# SimpleNode32.net
KiCad netlist of a schematic drawn in Altium Designer
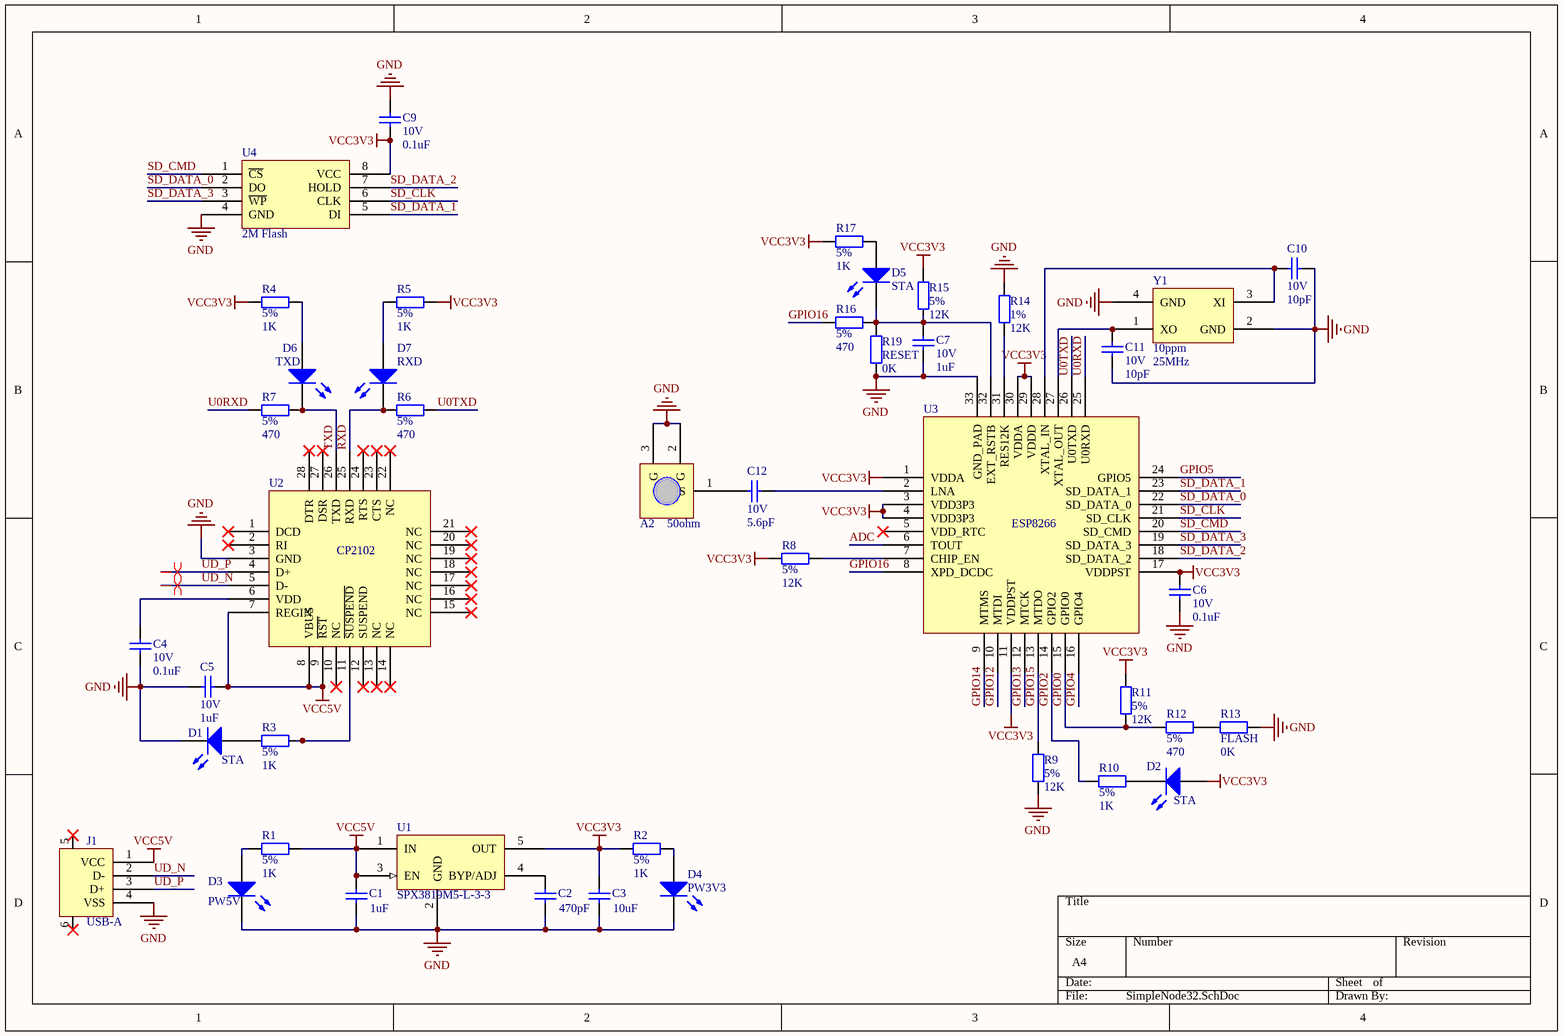
[diagram p0: SimpleNode32.SchDoc]

(export (version "E")
  (design (tool "Eeschema 10.0.6"))
  (components
    (comp (ref "A2")
      (value "50ohm")
      (footprint "IPEX-1 底座")
      (description "IPEX-1 底座")
      (libsource (lib "基础连接件") (part "IPEX-1 底座"))
    )
    (comp (ref "C1")
      (value "1uF")
      (footprint "C0402")
      (description "贴片无极性电容")
      (fields (field (name "Comment") "105"))
      (libsource (lib "基础元器件") (part "贴片无极性电容"))
    )
    (comp (ref "C2")
      (value "470pF")
      (footprint "C0402")
      (description "贴片无极性电容")
      (fields (field (name "Comment") "CAP"))
      (libsource (lib "基础元器件") (part "贴片无极性电容"))
    )
    (comp (ref "C3")
      (value "10uF")
      (footprint "C0402")
      (description "贴片无极性电容")
      (fields (field (name "Comment") "CAP"))
      (libsource (lib "基础元器件") (part "贴片无极性电容"))
    )
    (comp (ref "C4")
      (value "10V")
      (footprint "C0402")
      (description "贴片无极性电容")
      (fields (field (name "ALTIUM_VALUE") "0.1uF"))
      (libsource (lib "基础元器件") (part "贴片无极性电容"))
    )
    (comp (ref "C5")
      (value "10V")
      (footprint "C0402")
      (description "贴片无极性电容")
      (fields (field (name "ALTIUM_VALUE") "1uF"))
      (libsource (lib "基础元器件") (part "贴片无极性电容"))
    )
    (comp (ref "C6")
      (value "10V")
      (footprint "C0402")
      (description "贴片无极性电容")
      (fields (field (name "ALTIUM_VALUE") "0.1uF"))
      (libsource (lib "基础元器件") (part "贴片无极性电容"))
    )
    (comp (ref "C7")
      (value "10V")
      (footprint "C0402")
      (description "贴片无极性电容")
      (fields (field (name "ALTIUM_VALUE") "1uF"))
      (libsource (lib "基础元器件") (part "贴片无极性电容"))
    )
    (comp (ref "C9")
      (value "10V")
      (footprint "C0402")
      (description "贴片无极性电容")
      (fields (field (name "ALTIUM_VALUE") "0.1uF"))
      (libsource (lib "基础元器件") (part "贴片无极性电容"))
    )
    (comp (ref "C10")
      (value "10V")
      (footprint "C0402")
      (description "贴片无极性电容")
      (fields (field (name "ALTIUM_VALUE") "10pF"))
      (libsource (lib "基础元器件") (part "贴片无极性电容"))
    )
    (comp (ref "C11")
      (value "10V")
      (footprint "C0402")
      (description "贴片无极性电容")
      (fields (field (name "ALTIUM_VALUE") "10pF"))
      (libsource (lib "基础元器件") (part "贴片无极性电容"))
    )
    (comp (ref "C12")
      (value "10V")
      (footprint "C0402")
      (description "贴片无极性电容")
      (fields (field (name "ALTIUM_VALUE") "5.6pF"))
      (libsource (lib "基础元器件") (part "贴片无极性电容"))
    )
    (comp (ref "D1")
      (value "STA")
      (footprint "LED0402")
      (description "贴片发光二级管")
      (libsource (lib "基础元器件") (part "贴片发光二级管"))
    )
    (comp (ref "D2")
      (value "STA")
      (footprint "LED0402")
      (description "贴片发光二级管")
      (libsource (lib "基础元器件") (part "贴片发光二级管"))
    )
    (comp (ref "D3")
      (value "PW5V")
      (footprint "LED0402")
      (description "贴片发光二级管")
      (libsource (lib "基础元器件") (part "贴片发光二级管"))
    )
    (comp (ref "D4")
      (value "PW3V3")
      (footprint "LED0402")
      (description "贴片发光二级管")
      (libsource (lib "基础元器件") (part "贴片发光二级管"))
    )
    (comp (ref "D5")
      (value "STA")
      (footprint "LED0402")
      (description "贴片发光二级管")
      (libsource (lib "基础元器件") (part "贴片发光二级管"))
    )
    (comp (ref "D6")
      (value "TXD")
      (footprint "LED0402")
      (description "贴片发光二级管")
      (libsource (lib "基础元器件") (part "贴片发光二级管"))
    )
    (comp (ref "D7")
      (value "RXD")
      (footprint "LED0402")
      (description "贴片发光二级管")
      (libsource (lib "基础元器件") (part "贴片发光二级管"))
    )
    (comp (ref "J1")
      (value "USB-A")
      (footprint "USB 2.0 Type A 公头 沉板")
      (description "USB-A 公头")
      (libsource (lib "基础连接件") (part "USB-A 公头"))
    )
    (comp (ref "R1")
      (value "5%")
      (footprint "R0402")
      (description "贴片电阻")
      (fields (field (name "ALTIUM_VALUE") "1K"))
      (libsource (lib "") (part "贴片电阻_1"))
    )
    (comp (ref "R2")
      (value "5%")
      (footprint "R0402")
      (description "贴片电阻")
      (fields (field (name "ALTIUM_VALUE") "1K"))
      (libsource (lib "") (part "贴片电阻_1"))
    )
    (comp (ref "R3")
      (value "5%")
      (footprint "R0402")
      (description "贴片电阻")
      (fields (field (name "ALTIUM_VALUE") "1K"))
      (libsource (lib "") (part "贴片电阻_1"))
    )
    (comp (ref "R4")
      (value "5%")
      (footprint "R0402")
      (description "贴片电阻")
      (fields (field (name "ALTIUM_VALUE") "1K"))
      (libsource (lib "") (part "贴片电阻_1"))
    )
    (comp (ref "R5")
      (value "5%")
      (footprint "R0402")
      (description "贴片电阻")
      (fields (field (name "ALTIUM_VALUE") "1K"))
      (libsource (lib "") (part "贴片电阻_1"))
    )
    (comp (ref "R6")
      (value "5%")
      (footprint "R0402")
      (description "贴片电阻")
      (fields (field (name "ALTIUM_VALUE") "470"))
      (libsource (lib "") (part "贴片电阻_1"))
    )
    (comp (ref "R7")
      (value "5%")
      (footprint "R0402")
      (description "贴片电阻")
      (fields (field (name "ALTIUM_VALUE") "470"))
      (libsource (lib "") (part "贴片电阻_1"))
    )
    (comp (ref "R8")
      (value "5%")
      (footprint "R0402")
      (description "贴片电阻")
      (fields (field (name "ALTIUM_VALUE") "12K"))
      (libsource (lib "") (part "贴片电阻_2"))
    )
    (comp (ref "R9")
      (value "5%")
      (footprint "R0402")
      (description "贴片电阻")
      (fields (field (name "ALTIUM_VALUE") "12K"))
      (libsource (lib "基础元器件") (part "贴片电阻"))
    )
    (comp (ref "R10")
      (value "5%")
      (footprint "R0402")
      (description "贴片电阻")
      (fields (field (name "ALTIUM_VALUE") "1K"))
      (libsource (lib "") (part "贴片电阻_1"))
    )
    (comp (ref "R11")
      (value "5%")
      (footprint "R0402")
      (description "贴片电阻")
      (fields (field (name "ALTIUM_VALUE") "12K"))
      (libsource (lib "基础元器件") (part "贴片电阻"))
    )
    (comp (ref "R12")
      (value "5%")
      (footprint "R0402")
      (description "贴片电阻")
      (fields (field (name "ALTIUM_VALUE") "470"))
      (libsource (lib "") (part "贴片电阻_2"))
    )
    (comp (ref "R13")
      (value "FLASH")
      (footprint "R0402")
      (description "贴片电阻")
      (fields (field (name "ALTIUM_VALUE") "0K"))
      (libsource (lib "") (part "贴片电阻_1"))
    )
    (comp (ref "R14")
      (value "1%")
      (footprint "R0402")
      (description "贴片电阻")
      (fields (field (name "ALTIUM_VALUE") "12K"))
      (libsource (lib "基础元器件") (part "贴片电阻"))
    )
    (comp (ref "R15")
      (value "5%")
      (footprint "R0402")
      (description "贴片电阻")
      (fields (field (name "ALTIUM_VALUE") "12K"))
      (libsource (lib "基础元器件") (part "贴片电阻"))
    )
    (comp (ref "R16")
      (value "5%")
      (footprint "R0402")
      (description "贴片电阻")
      (fields (field (name "ALTIUM_VALUE") "470"))
      (libsource (lib "") (part "贴片电阻_1"))
    )
    (comp (ref "R17")
      (value "5%")
      (footprint "R0402")
      (description "贴片电阻")
      (fields (field (name "ALTIUM_VALUE") "1K"))
      (libsource (lib "") (part "贴片电阻_2"))
    )
    (comp (ref "R19")
      (value "RESET")
      (footprint "R0402")
      (description "贴片电阻")
      (fields (field (name "ALTIUM_VALUE") "0K"))
      (libsource (lib "基础元器件") (part "贴片电阻"))
    )
    (comp (ref "U1")
      (value "SPX3819M5-L-3-3")
      (footprint "SOT25-5")
      (description "贴片5V转3.3V芯片")
      (libsource (lib "基础元器件") (part "SPX3819M5-L-3-3"))
    )
    (comp (ref "U2")
      (value "CP2102")
      (footprint "MLP28")
      (description "贴片USB转TTL")
      (libsource (lib "基础元器件") (part "CP2102"))
    )
    (comp (ref "U3")
      (value "ESP8266")
      (footprint "QFN32L")
      (description "ESP8266无线WiFi芯片")
      (libsource (lib "基础元器件") (part "ESP8266"))
    )
    (comp (ref "U4")
      (value "2M Flash")
      (footprint "SOP8")
      (description "贴片2M存储Flash芯片")
      (libsource (lib "基础元器件") (part "GD25Q16CSIG"))
    )
    (comp (ref "Y1")
      (value "10ppm")
      (footprint "XTAL-2520")
      (description "贴片无源晶振")
      (fields (field (name "ALTIUM_VALUE") "25MHz"))
      (libsource (lib "基础元器件") (part "贴片无源晶振"))
    )
  )
  (nets
    (net (code "1") (name "/ADC") (class "Default")
      (node (ref "U3") (pin "6") (pinfunction "TOUT_6") (pintype "passive"))
    )
    (net (code "2") (name "/GPIO0") (class "Default")
      (node (ref "R11") (pin "1") (pinfunction "1_1") (pintype "passive"))
      (node (ref "R12") (pin "1") (pinfunction "1_1") (pintype "passive"))
      (node (ref "U3") (pin "15") (pinfunction "GPIO0_15") (pintype "passive"))
    )
    (net (code "3") (name "/GPIO2") (class "Default")
      (node (ref "R10") (pin "2") (pinfunction "2_2") (pintype "passive"))
      (node (ref "U3") (pin "14") (pinfunction "GPIO2_14") (pintype "passive"))
    )
    (net (code "4") (name "/GPIO4") (class "Default")
      (node (ref "U3") (pin "16") (pinfunction "GPIO4_16") (pintype "passive"))
    )
    (net (code "5") (name "/GPIO5") (class "Default")
      (node (ref "U3") (pin "24") (pinfunction "GPIO5_24") (pintype "passive"))
    )
    (net (code "6") (name "/GPIO12") (class "Default")
      (node (ref "U3") (pin "10") (pinfunction "MTDI_10") (pintype "passive"))
    )
    (net (code "7") (name "/GPIO13") (class "Default")
      (node (ref "U3") (pin "12") (pinfunction "MTCK_12") (pintype "passive"))
    )
    (net (code "8") (name "/GPIO14") (class "Default")
      (node (ref "U3") (pin "9") (pinfunction "MTMS_9") (pintype "passive"))
    )
    (net (code "9") (name "/GPIO15") (class "Default")
      (node (ref "R9") (pin "2") (pinfunction "2_2") (pintype "passive"))
      (node (ref "U3") (pin "13") (pinfunction "MTDO_13") (pintype "passive"))
    )
    (net (code "10") (name "/GPIO16") (class "Default")
      (node (ref "R16") (pin "2") (pinfunction "2_2") (pintype "passive"))
      (node (ref "U3") (pin "8") (pinfunction "XPD_DCDC_8") (pintype "passive"))
    )
    (net (code "11") (name "/RXD") (class "Default")
      (node (ref "D7") (pin "2") (pinfunction "K_2") (pintype "passive"))
      (node (ref "R6") (pin "2") (pinfunction "2_2") (pintype "passive"))
      (node (ref "U2") (pin "25") (pinfunction "RXD_25") (pintype "passive"))
    )
    (net (code "12") (name "/SD_CLK") (class "Default")
      (node (ref "U3") (pin "21") (pinfunction "SD_CLK_21") (pintype "passive"))
      (node (ref "U4") (pin "6") (pinfunction "CLK_6") (pintype "passive"))
    )
    (net (code "13") (name "/SD_CMD") (class "Default")
      (node (ref "U3") (pin "20") (pinfunction "SD_CMD_20") (pintype "passive"))
      (node (ref "U4") (pin "1") (pinfunction "~{CS}_1") (pintype "passive"))
    )
    (net (code "14") (name "/SD_DATA_0") (class "Default")
      (node (ref "U3") (pin "22") (pinfunction "SD_DATA_0_22") (pintype "passive"))
      (node (ref "U4") (pin "2") (pinfunction "DO_2") (pintype "passive"))
    )
    (net (code "15") (name "/SD_DATA_1") (class "Default")
      (node (ref "U3") (pin "23") (pinfunction "SD_DATA_1_23") (pintype "passive"))
      (node (ref "U4") (pin "5") (pinfunction "DI_5") (pintype "passive"))
    )
    (net (code "16") (name "/SD_DATA_2") (class "Default")
      (node (ref "U3") (pin "18") (pinfunction "SD_DATA_2_18") (pintype "passive"))
      (node (ref "U4") (pin "7") (pinfunction "HOLD_7") (pintype "passive"))
    )
    (net (code "17") (name "/SD_DATA_3") (class "Default")
      (node (ref "U3") (pin "19") (pinfunction "SD_DATA_3_19") (pintype "passive"))
      (node (ref "U4") (pin "3") (pinfunction "~{WP}_3") (pintype "passive"))
    )
    (net (code "18") (name "/TXD") (class "Default")
      (node (ref "D6") (pin "2") (pinfunction "K_2") (pintype "passive"))
      (node (ref "R7") (pin "1") (pinfunction "1_1") (pintype "passive"))
      (node (ref "U2") (pin "26") (pinfunction "TXD_26") (pintype "passive"))
    )
    (net (code "19") (name "/U0RXD") (class "Default")
      (node (ref "R7") (pin "2") (pinfunction "2_2") (pintype "passive"))
      (node (ref "U3") (pin "25") (pinfunction "U0RXD_25") (pintype "passive"))
    )
    (net (code "20") (name "/U0TXD") (class "Default")
      (node (ref "R6") (pin "1") (pinfunction "1_1") (pintype "passive"))
      (node (ref "U3") (pin "26") (pinfunction "U0TXD_26") (pintype "passive"))
    )
    (net (code "21") (name "/UD_N") (class "Default")
      (node (ref "J1") (pin "2") (pinfunction "D-_2") (pintype "passive"))
      (node (ref "U2") (pin "5") (pinfunction "D-_5") (pintype "passive"))
    )
    (net (code "22") (name "/UD_P") (class "Default")
      (node (ref "J1") (pin "3") (pinfunction "D+_3") (pintype "passive"))
      (node (ref "U2") (pin "4") (pinfunction "D+_4") (pintype "passive"))
    )
    (net (code "23") (name "GND") (class "Default")
      (node (ref "A2") (pin "2") (pinfunction "G_2") (pintype "passive"))
      (node (ref "A2") (pin "3") (pinfunction "G_3") (pintype "passive"))
      (node (ref "C1") (pin "1") (pinfunction "1_1") (pintype "passive"))
      (node (ref "C10") (pin "2") (pinfunction "2_2") (pintype "passive"))
      (node (ref "C11") (pin "2") (pinfunction "2_2") (pintype "passive"))
      (node (ref "C2") (pin "1") (pinfunction "1_1") (pintype "passive"))
      (node (ref "C3") (pin "1") (pinfunction "1_1") (pintype "passive"))
      (node (ref "C4") (pin "1") (pinfunction "1_1") (pintype "passive"))
      (node (ref "C5") (pin "2") (pinfunction "2_2") (pintype "passive"))
      (node (ref "C6") (pin "1") (pinfunction "1_1") (pintype "passive"))
      (node (ref "C7") (pin "1") (pinfunction "1_1") (pintype "passive"))
      (node (ref "C9") (pin "1") (pinfunction "1_1") (pintype "passive"))
      (node (ref "D1") (pin "2") (pinfunction "K_2") (pintype "passive"))
      (node (ref "D3") (pin "2") (pinfunction "K_2") (pintype "passive"))
      (node (ref "D4") (pin "2") (pinfunction "K_2") (pintype "passive"))
      (node (ref "J1") (pin "4") (pinfunction "VSS_4") (pintype "passive"))
      (node (ref "R13") (pin "1") (pinfunction "1_1") (pintype "passive"))
      (node (ref "R14") (pin "2") (pinfunction "2_2") (pintype "passive"))
      (node (ref "R19") (pin "1") (pinfunction "1_1") (pintype "passive"))
      (node (ref "R9") (pin "1") (pinfunction "1_1") (pintype "passive"))
      (node (ref "U1") (pin "2") (pinfunction "GND_2") (pintype "power_in"))
      (node (ref "U2") (pin "3") (pinfunction "GND_3") (pintype "passive"))
      (node (ref "U3") (pin "33") (pinfunction "GND_PAD_33") (pintype "passive"))
      (node (ref "U4") (pin "4") (pinfunction "GND_4") (pintype "passive"))
      (node (ref "Y1") (pin "2") (pinfunction "GND_2") (pintype "passive"))
      (node (ref "Y1") (pin "4") (pinfunction "GND_4") (pintype "passive"))
    )
    (net (code "24") (name "Net-(A2-S)") (class "Default")
      (node (ref "A2") (pin "1") (pinfunction "S_1") (pintype "passive"))
      (node (ref "C12") (pin "1") (pinfunction "1_1") (pintype "passive"))
    )
    (net (code "25") (name "Net-(D1-A)") (class "Default")
      (node (ref "D1") (pin "1") (pinfunction "A_1") (pintype "passive"))
      (node (ref "R3") (pin "2") (pinfunction "2_2") (pintype "passive"))
    )
    (net (code "26") (name "Net-(D2-K)") (class "Default")
      (node (ref "D2") (pin "2") (pinfunction "K_2") (pintype "passive"))
      (node (ref "R10") (pin "1") (pinfunction "1_1") (pintype "passive"))
    )
    (net (code "27") (name "Net-(D3-A)") (class "Default")
      (node (ref "D3") (pin "1") (pinfunction "A_1") (pintype "passive"))
      (node (ref "R1") (pin "2") (pinfunction "2_2") (pintype "passive"))
    )
    (net (code "28") (name "Net-(D4-A)") (class "Default")
      (node (ref "D4") (pin "1") (pinfunction "A_1") (pintype "passive"))
      (node (ref "R2") (pin "1") (pinfunction "1_1") (pintype "passive"))
    )
    (net (code "29") (name "Net-(D5-A)") (class "Default")
      (node (ref "D5") (pin "1") (pinfunction "A_1") (pintype "passive"))
      (node (ref "R17") (pin "2") (pinfunction "2_2") (pintype "passive"))
    )
    (net (code "30") (name "Net-(D5-K)") (class "Default")
      (node (ref "C7") (pin "2") (pinfunction "2_2") (pintype "passive"))
      (node (ref "D5") (pin "2") (pinfunction "K_2") (pintype "passive"))
      (node (ref "R15") (pin "1") (pinfunction "1_1") (pintype "passive"))
      (node (ref "R16") (pin "1") (pinfunction "1_1") (pintype "passive"))
      (node (ref "R19") (pin "2") (pinfunction "2_2") (pintype "passive"))
      (node (ref "U3") (pin "32") (pinfunction "EXT_RSTB_32") (pintype "passive"))
    )
    (net (code "31") (name "Net-(D6-A)") (class "Default")
      (node (ref "D6") (pin "1") (pinfunction "A_1") (pintype "passive"))
      (node (ref "R4") (pin "1") (pinfunction "1_1") (pintype "passive"))
    )
    (net (code "32") (name "Net-(D7-A)") (class "Default")
      (node (ref "D7") (pin "1") (pinfunction "A_1") (pintype "passive"))
      (node (ref "R5") (pin "2") (pinfunction "2_2") (pintype "passive"))
    )
    (net (code "33") (name "Net-(R12-Pad2)") (class "Default")
      (node (ref "R12") (pin "2") (pinfunction "2_2") (pintype "passive"))
      (node (ref "R13") (pin "2") (pinfunction "2_2") (pintype "passive"))
    )
    (net (code "34") (name "Net-(U1-BYP{slash}ADJ)") (class "Default")
      (node (ref "C2") (pin "2") (pinfunction "2_2") (pintype "passive"))
      (node (ref "U1") (pin "4") (pinfunction "BYP/ADJ_4") (pintype "passive"))
    )
    (net (code "35") (name "Net-(U2-VDD)") (class "Default")
      (node (ref "C4") (pin "2") (pinfunction "2_2") (pintype "passive"))
      (node (ref "U2") (pin "6") (pinfunction "VDD_6") (pintype "passive"))
    )
    (net (code "36") (name "Net-(U2-~{SUSPEND})") (class "Default")
      (node (ref "R3") (pin "1") (pinfunction "1_1") (pintype "passive"))
      (node (ref "U2") (pin "11") (pinfunction "~{SUSPEND}_11") (pintype "passive"))
    )
    (net (code "37") (name "Net-(U3-CHIP_EN)") (class "Default")
      (node (ref "R8") (pin "2") (pinfunction "2_2") (pintype "passive"))
      (node (ref "U3") (pin "7") (pinfunction "CHIP_EN_7") (pintype "passive"))
    )
    (net (code "38") (name "Net-(U3-LNA)") (class "Default")
      (node (ref "C12") (pin "2") (pinfunction "2_2") (pintype "passive"))
      (node (ref "U3") (pin "2") (pinfunction "LNA_2") (pintype "passive"))
    )
    (net (code "39") (name "Net-(U3-RES12K)") (class "Default")
      (node (ref "R14") (pin "1") (pinfunction "1_1") (pintype "passive"))
      (node (ref "U3") (pin "31") (pinfunction "RES12K_31") (pintype "passive"))
    )
    (net (code "40") (name "Net-(U3-XTAL_IN)") (class "Default")
      (node (ref "C10") (pin "1") (pinfunction "1_1") (pintype "passive"))
      (node (ref "U3") (pin "28") (pinfunction "XTAL_IN_28") (pintype "passive"))
      (node (ref "Y1") (pin "3") (pinfunction "XI_3") (pintype "passive"))
    )
    (net (code "41") (name "Net-(U3-XTAL_OUT)") (class "Default")
      (node (ref "C11") (pin "1") (pinfunction "1_1") (pintype "passive"))
      (node (ref "U3") (pin "27") (pinfunction "XTAL_OUT_27") (pintype "passive"))
      (node (ref "Y1") (pin "1") (pinfunction "XO_1") (pintype "passive"))
    )
    (net (code "42") (name "VCC3V3") (class "Default")
      (node (ref "C3") (pin "2") (pinfunction "2_2") (pintype "passive"))
      (node (ref "C6") (pin "2") (pinfunction "2_2") (pintype "passive"))
      (node (ref "C9") (pin "2") (pinfunction "2_2") (pintype "passive"))
      (node (ref "D2") (pin "1") (pinfunction "A_1") (pintype "passive"))
      (node (ref "R11") (pin "2") (pinfunction "2_2") (pintype "passive"))
      (node (ref "R15") (pin "2") (pinfunction "2_2") (pintype "passive"))
      (node (ref "R17") (pin "1") (pinfunction "1_1") (pintype "passive"))
      (node (ref "R2") (pin "2") (pinfunction "2_2") (pintype "passive"))
      (node (ref "R4") (pin "2") (pinfunction "2_2") (pintype "passive"))
      (node (ref "R5") (pin "1") (pinfunction "1_1") (pintype "passive"))
      (node (ref "R8") (pin "1") (pinfunction "1_1") (pintype "passive"))
      (node (ref "U1") (pin "5") (pinfunction "OUT_5") (pintype "power_in"))
      (node (ref "U3") (pin "1") (pinfunction "VDDA_1") (pintype "passive"))
      (node (ref "U3") (pin "11") (pinfunction "VDDPST_11") (pintype "passive"))
      (node (ref "U3") (pin "17") (pinfunction "VDDPST_17") (pintype "passive"))
      (node (ref "U3") (pin "29") (pinfunction "VDDD_29") (pintype "passive"))
      (node (ref "U3") (pin "3") (pinfunction "VDD3P3_3") (pintype "passive"))
      (node (ref "U3") (pin "30") (pinfunction "VDDA_30") (pintype "passive"))
      (node (ref "U3") (pin "4") (pinfunction "VDD3P3_4") (pintype "passive"))
      (node (ref "U4") (pin "8") (pinfunction "VCC_8") (pintype "power_in"))
    )
    (net (code "43") (name "VCC5V") (class "Default")
      (node (ref "C1") (pin "2") (pinfunction "2_2") (pintype "passive"))
      (node (ref "C5") (pin "1") (pinfunction "1_1") (pintype "passive"))
      (node (ref "J1") (pin "1") (pinfunction "VCC_1") (pintype "passive"))
      (node (ref "R1") (pin "1") (pinfunction "1_1") (pintype "passive"))
      (node (ref "U1") (pin "1") (pinfunction "IN_1") (pintype "power_in"))
      (node (ref "U1") (pin "3") (pinfunction "EN_3") (pintype "input"))
      (node (ref "U2") (pin "7") (pinfunction "REGIN_7") (pintype "passive"))
      (node (ref "U2") (pin "8") (pinfunction "VBUS_8") (pintype "passive"))
      (node (ref "U2") (pin "9") (pinfunction "~{RST}_9") (pintype "passive"))
    )
    (net (code "44") (name "unconnected-(J1-Pad5)") (class "Default")
      (node (ref "J1") (pin "5") (pinfunction "5_5") (pintype "passive+no_connect"))
    )
    (net (code "45") (name "unconnected-(J1-Pad6)") (class "Default")
      (node (ref "J1") (pin "6") (pinfunction "6_6") (pintype "passive+no_connect"))
    )
    (net (code "46") (name "unconnected-(U2-CTS-Pad23)") (class "Default")
      (node (ref "U2") (pin "23") (pinfunction "CTS_23") (pintype "passive+no_connect"))
    )
    (net (code "47") (name "unconnected-(U2-DCD-Pad1)") (class "Default")
      (node (ref "U2") (pin "1") (pinfunction "DCD_1") (pintype "passive+no_connect"))
    )
    (net (code "48") (name "unconnected-(U2-DSR-Pad27)") (class "Default")
      (node (ref "U2") (pin "27") (pinfunction "DSR_27") (pintype "passive+no_connect"))
    )
    (net (code "49") (name "unconnected-(U2-DTR-Pad28)") (class "Default")
      (node (ref "U2") (pin "28") (pinfunction "DTR_28") (pintype "passive+no_connect"))
    )
    (net (code "50") (name "unconnected-(U2-NC-Pad10)") (class "Default")
      (node (ref "U2") (pin "10") (pinfunction "NC_10") (pintype "passive+no_connect"))
    )
    (net (code "51") (name "unconnected-(U2-NC-Pad13)") (class "Default")
      (node (ref "U2") (pin "13") (pinfunction "NC_13") (pintype "passive+no_connect"))
    )
    (net (code "52") (name "unconnected-(U2-NC-Pad14)") (class "Default")
      (node (ref "U2") (pin "14") (pinfunction "NC_14") (pintype "passive+no_connect"))
    )
    (net (code "53") (name "unconnected-(U2-NC-Pad15)") (class "Default")
      (node (ref "U2") (pin "15") (pinfunction "NC_15") (pintype "passive+no_connect"))
    )
    (net (code "54") (name "unconnected-(U2-NC-Pad16)") (class "Default")
      (node (ref "U2") (pin "16") (pinfunction "NC_16") (pintype "passive+no_connect"))
    )
    (net (code "55") (name "unconnected-(U2-NC-Pad17)") (class "Default")
      (node (ref "U2") (pin "17") (pinfunction "NC_17") (pintype "passive+no_connect"))
    )
    (net (code "56") (name "unconnected-(U2-NC-Pad18)") (class "Default")
      (node (ref "U2") (pin "18") (pinfunction "NC_18") (pintype "passive+no_connect"))
    )
    (net (code "57") (name "unconnected-(U2-NC-Pad19)") (class "Default")
      (node (ref "U2") (pin "19") (pinfunction "NC_19") (pintype "passive+no_connect"))
    )
    (net (code "58") (name "unconnected-(U2-NC-Pad20)") (class "Default")
      (node (ref "U2") (pin "20") (pinfunction "NC_20") (pintype "passive+no_connect"))
    )
    (net (code "59") (name "unconnected-(U2-NC-Pad21)") (class "Default")
      (node (ref "U2") (pin "21") (pinfunction "NC_21") (pintype "passive+no_connect"))
    )
    (net (code "60") (name "unconnected-(U2-NC-Pad22)") (class "Default")
      (node (ref "U2") (pin "22") (pinfunction "NC_22") (pintype "passive+no_connect"))
    )
    (net (code "61") (name "unconnected-(U2-RI-Pad2)") (class "Default")
      (node (ref "U2") (pin "2") (pinfunction "RI_2") (pintype "passive+no_connect"))
    )
    (net (code "62") (name "unconnected-(U2-RTS-Pad24)") (class "Default")
      (node (ref "U2") (pin "24") (pinfunction "RTS_24") (pintype "passive+no_connect"))
    )
    (net (code "63") (name "unconnected-(U2-SUSPEND-Pad12)") (class "Default")
      (node (ref "U2") (pin "12") (pinfunction "SUSPEND_12") (pintype "passive+no_connect"))
    )
    (net (code "64") (name "unconnected-(U3-VDD_RTC-Pad5)") (class "Default")
      (node (ref "U3") (pin "5") (pinfunction "VDD_RTC_5") (pintype "passive+no_connect"))
    )
  )
)
